# teensyLC-midi-IO_02.net
KiCad netlist of a schematic drawn in EAGLE
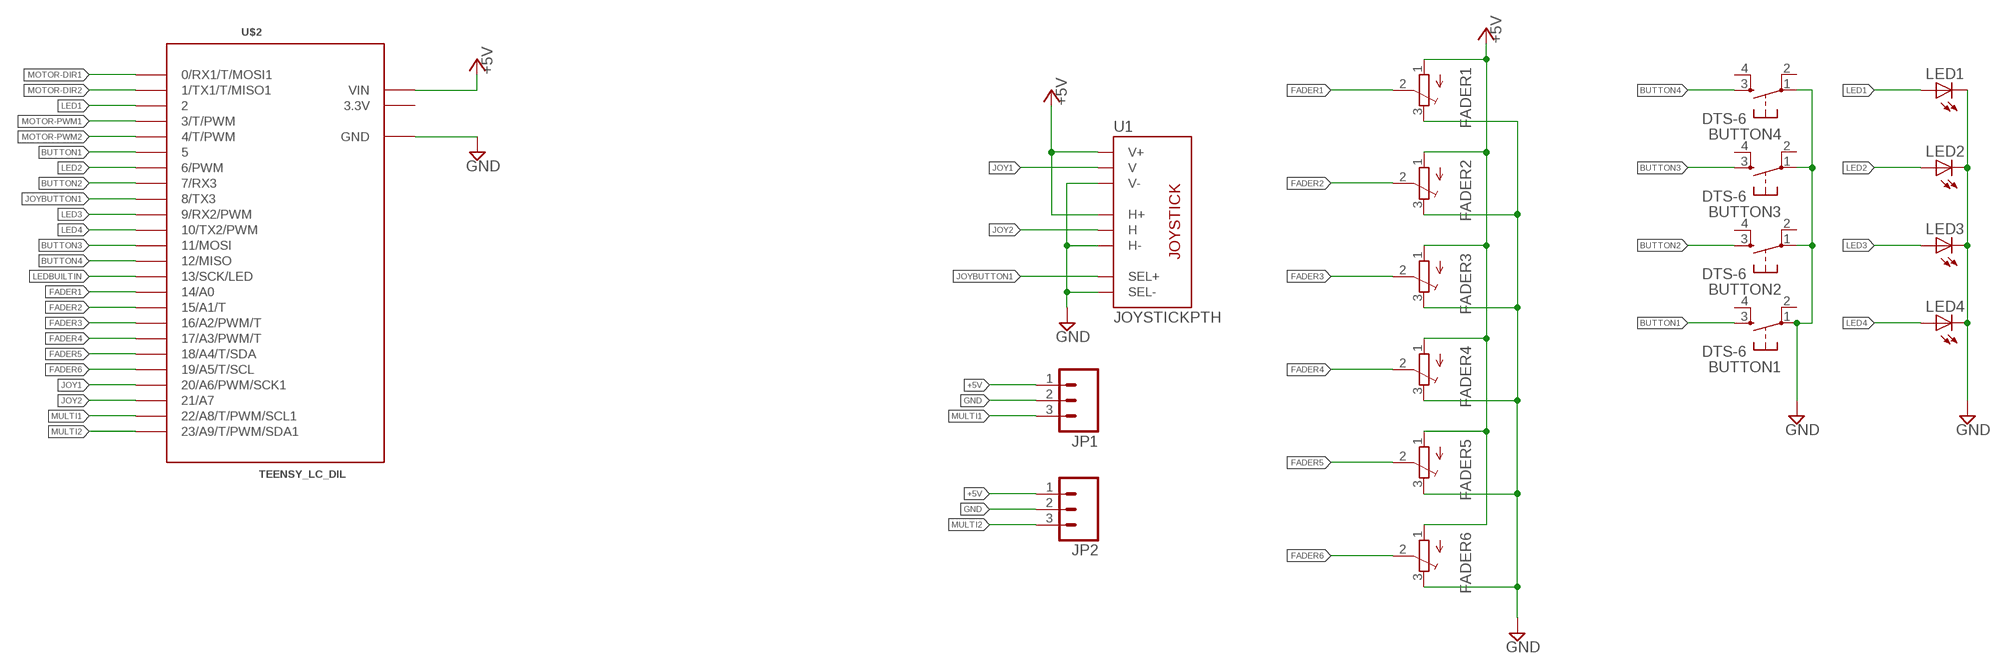
[diagram p0: schematic, sheet 1]

(export (version "E")
  (design (tool "Eeschema 10.0.6"))
  (components
    (comp (ref "BUTTON1")
      (value "DTS-6")
      (footprint "eagle-import:DTS-6")
      (libsource (lib "eagle-import") (part "DTS-6"))
    )
    (comp (ref "BUTTON2")
      (value "DTS-6")
      (footprint "eagle-import:DTS-6")
      (libsource (lib "eagle-import") (part "DTS-6"))
    )
    (comp (ref "BUTTON3")
      (value "DTS-6")
      (footprint "eagle-import:DTS-6")
      (libsource (lib "eagle-import") (part "DTS-6"))
    )
    (comp (ref "BUTTON4")
      (value "DTS-6")
      (footprint "eagle-import:DTS-6")
      (libsource (lib "eagle-import") (part "DTS-6"))
    )
    (comp (ref "FADER1")
      (value "TRIMPOT3386")
      (footprint "eagle-import:TRIM-3386")
      (libsource (lib "eagle-import") (part "TRIMPOT3386"))
    )
    (comp (ref "FADER2")
      (value "TRIMPOT3386")
      (footprint "eagle-import:TRIM-3386")
      (libsource (lib "eagle-import") (part "TRIMPOT3386"))
    )
    (comp (ref "FADER3")
      (value "TRIMPOT3386")
      (footprint "eagle-import:TRIM-3386")
      (libsource (lib "eagle-import") (part "TRIMPOT3386"))
    )
    (comp (ref "FADER4")
      (value "TRIMPOT3386")
      (footprint "eagle-import:TRIM-3386")
      (libsource (lib "eagle-import") (part "TRIMPOT3386"))
    )
    (comp (ref "FADER5")
      (value "TRIMPOT3386")
      (footprint "eagle-import:TRIM-3386")
      (libsource (lib "eagle-import") (part "TRIMPOT3386"))
    )
    (comp (ref "FADER6")
      (value "TRIMPOT3386")
      (footprint "eagle-import:TRIM-3386")
      (libsource (lib "eagle-import") (part "TRIMPOT3386"))
    )
    (comp (ref "JP1")
      (value "M03LOCK")
      (footprint "eagle-import:1X03_LOCK")
      (libsource (lib "eagle-import") (part "M03LOCK"))
    )
    (comp (ref "JP2")
      (value "M03LOCK")
      (footprint "eagle-import:1X03_LOCK")
      (libsource (lib "eagle-import") (part "M03LOCK"))
    )
    (comp (ref "LED1")
      (value "LED5MM")
      (footprint "eagle-import:LED5MM")
      (libsource (lib "eagle-import") (part "LED5MM"))
    )
    (comp (ref "LED2")
      (value "LED5MM")
      (footprint "eagle-import:LED5MM")
      (libsource (lib "eagle-import") (part "LED5MM"))
    )
    (comp (ref "LED3")
      (value "LED5MM")
      (footprint "eagle-import:LED5MM")
      (libsource (lib "eagle-import") (part "LED5MM"))
    )
    (comp (ref "LED4")
      (value "LED5MM")
      (footprint "eagle-import:LED5MM")
      (libsource (lib "eagle-import") (part "LED5MM"))
    )
    (comp (ref "U$2")
      (value "TEENSY_LC_DIL")
      (footprint "eagle-import:TEENSY_3.0-3.2&LC_DIL")
      (libsource (lib "eagle-import") (part "TEENSY_LC_DIL"))
    )
    (comp (ref "U1")
      (value "JOYSTICKPTH")
      (footprint "eagle-import:JOYSTICK")
      (libsource (lib "eagle-import") (part "JOYSTICKPTH"))
    )
  )
  (nets
    (net (code "1") (name "+5V") (class "Default")
      (node (ref "FADER1") (pin "1") (pinfunction "A_1") (pintype "passive"))
      (node (ref "FADER2") (pin "1") (pinfunction "A_1") (pintype "passive"))
      (node (ref "FADER3") (pin "1") (pinfunction "A_1") (pintype "passive"))
      (node (ref "FADER4") (pin "1") (pinfunction "A_1") (pintype "passive"))
      (node (ref "FADER5") (pin "1") (pinfunction "A_1") (pintype "passive"))
      (node (ref "FADER6") (pin "1") (pinfunction "A_1") (pintype "passive"))
      (node (ref "JP1") (pin "1") (pinfunction "1_1") (pintype "passive"))
      (node (ref "JP2") (pin "1") (pinfunction "1_1") (pintype "passive"))
      (node (ref "U$2") (pin "VIN") (pinfunction "VIN_VIN") (pintype "power_in"))
      (node (ref "U1") (pin "H1") (pinfunction "H+_H1") (pintype "bidirectional"))
      (node (ref "U1") (pin "V1") (pinfunction "V+_V1") (pintype "bidirectional"))
    )
    (net (code "2") (name "/3.3V") (class "Default")
      (node (ref "U$2") (pin "3.3V") (pinfunction "3.3V_3.3V") (pintype "power_in"))
    )
    (net (code "3") (name "BUTTON1") (class "Default")
      (node (ref "BUTTON1") (pin "3") (pinfunction "3_3") (pintype "passive"))
      (node (ref "U$2") (pin "5") (pinfunction "5_5") (pintype "bidirectional"))
    )
    (net (code "4") (name "BUTTON2") (class "Default")
      (node (ref "BUTTON2") (pin "3") (pinfunction "3_3") (pintype "passive"))
      (node (ref "U$2") (pin "7") (pinfunction "7/RX3_7") (pintype "bidirectional"))
    )
    (net (code "5") (name "BUTTON3") (class "Default")
      (node (ref "BUTTON3") (pin "3") (pinfunction "3_3") (pintype "passive"))
      (node (ref "U$2") (pin "11") (pinfunction "11/MOSI_11") (pintype "bidirectional"))
    )
    (net (code "6") (name "BUTTON4") (class "Default")
      (node (ref "BUTTON4") (pin "3") (pinfunction "3_3") (pintype "passive"))
      (node (ref "U$2") (pin "12") (pinfunction "12/MISO_12") (pintype "bidirectional"))
    )
    (net (code "7") (name "FADER1") (class "Default")
      (node (ref "FADER1") (pin "2") (pinfunction "S_2") (pintype "passive"))
      (node (ref "U$2") (pin "14/A0") (pinfunction "14/A0_14/A0") (pintype "bidirectional"))
    )
    (net (code "8") (name "FADER2") (class "Default")
      (node (ref "FADER2") (pin "2") (pinfunction "S_2") (pintype "passive"))
      (node (ref "U$2") (pin "15/A1") (pinfunction "15/A1/T_15/A1") (pintype "bidirectional"))
    )
    (net (code "9") (name "FADER3") (class "Default")
      (node (ref "FADER3") (pin "2") (pinfunction "S_2") (pintype "passive"))
      (node (ref "U$2") (pin "16/A2") (pinfunction "16/A2/PWM/T_16/A2") (pintype "bidirectional"))
    )
    (net (code "10") (name "FADER4") (class "Default")
      (node (ref "FADER4") (pin "2") (pinfunction "S_2") (pintype "passive"))
      (node (ref "U$2") (pin "17/A3") (pinfunction "17/A3/PWM/T_17/A3") (pintype "bidirectional"))
    )
    (net (code "11") (name "FADER5") (class "Default")
      (node (ref "FADER5") (pin "2") (pinfunction "S_2") (pintype "passive"))
      (node (ref "U$2") (pin "18/A4") (pinfunction "18/A4/T/SDA_18/A4") (pintype "bidirectional"))
    )
    (net (code "12") (name "FADER6") (class "Default")
      (node (ref "FADER6") (pin "2") (pinfunction "S_2") (pintype "passive"))
      (node (ref "U$2") (pin "19/A5") (pinfunction "19/A5/T/SCL_19/A5") (pintype "bidirectional"))
    )
    (net (code "13") (name "GND") (class "Default")
      (node (ref "BUTTON1") (pin "1") (pinfunction "1_1") (pintype "passive"))
      (node (ref "BUTTON2") (pin "1") (pinfunction "1_1") (pintype "passive"))
      (node (ref "BUTTON3") (pin "1") (pinfunction "1_1") (pintype "passive"))
      (node (ref "BUTTON4") (pin "1") (pinfunction "1_1") (pintype "passive"))
      (node (ref "FADER1") (pin "3") (pinfunction "E_3") (pintype "passive"))
      (node (ref "FADER2") (pin "3") (pinfunction "E_3") (pintype "passive"))
      (node (ref "FADER3") (pin "3") (pinfunction "E_3") (pintype "passive"))
      (node (ref "FADER4") (pin "3") (pinfunction "E_3") (pintype "passive"))
      (node (ref "FADER5") (pin "3") (pinfunction "E_3") (pintype "passive"))
      (node (ref "FADER6") (pin "3") (pinfunction "E_3") (pintype "passive"))
      (node (ref "JP1") (pin "2") (pinfunction "2_2") (pintype "passive"))
      (node (ref "JP2") (pin "2") (pinfunction "2_2") (pintype "passive"))
      (node (ref "LED1") (pin "K") (pinfunction "C_K") (pintype "passive"))
      (node (ref "LED2") (pin "K") (pinfunction "C_K") (pintype "passive"))
      (node (ref "LED3") (pin "K") (pinfunction "C_K") (pintype "passive"))
      (node (ref "LED4") (pin "K") (pinfunction "C_K") (pintype "passive"))
      (node (ref "U$2") (pin "AGND") (pinfunction "GND_AGND") (pintype "power_in"))
      (node (ref "U$2") (pin "GND") (pinfunction "GND_GND") (pintype "power_in"))
      (node (ref "U1") (pin "B2A") (pinfunction "SEL-_B2A") (pintype "bidirectional"))
      (node (ref "U1") (pin "H3") (pinfunction "H-_H3") (pintype "bidirectional"))
      (node (ref "U1") (pin "V3") (pinfunction "V-_V3") (pintype "bidirectional"))
    )
    (net (code "14") (name "JOY1") (class "Default")
      (node (ref "U$2") (pin "20/A6") (pinfunction "20/A6/PWM/SCK1_20/A6") (pintype "bidirectional"))
      (node (ref "U1") (pin "V2") (pinfunction "V_V2") (pintype "bidirectional"))
    )
    (net (code "15") (name "JOY2") (class "Default")
      (node (ref "U$2") (pin "21/A7") (pinfunction "21/A7_21/A7") (pintype "bidirectional"))
      (node (ref "U1") (pin "H2") (pinfunction "H_H2") (pintype "bidirectional"))
    )
    (net (code "16") (name "JOYBUTTON1") (class "Default")
      (node (ref "U$2") (pin "8") (pinfunction "8/TX3_8") (pintype "bidirectional"))
      (node (ref "U1") (pin "B1A") (pinfunction "SEL+_B1A") (pintype "bidirectional"))
    )
    (net (code "17") (name "LED1") (class "Default")
      (node (ref "LED1") (pin "A") (pinfunction "A_A") (pintype "passive"))
      (node (ref "U$2") (pin "2") (pinfunction "2_2") (pintype "bidirectional"))
    )
    (net (code "18") (name "LED2") (class "Default")
      (node (ref "LED2") (pin "A") (pinfunction "A_A") (pintype "passive"))
      (node (ref "U$2") (pin "6") (pinfunction "6/PWM_6") (pintype "bidirectional"))
    )
    (net (code "19") (name "LED3") (class "Default")
      (node (ref "LED3") (pin "A") (pinfunction "A_A") (pintype "passive"))
      (node (ref "U$2") (pin "9") (pinfunction "9/RX2/PWM_9") (pintype "bidirectional"))
    )
    (net (code "20") (name "LED4") (class "Default")
      (node (ref "LED4") (pin "A") (pinfunction "A_A") (pintype "passive"))
      (node (ref "U$2") (pin "10") (pinfunction "10/TX2/PWM_10") (pintype "bidirectional"))
    )
    (net (code "21") (name "LEDBUILTIN") (class "Default")
      (node (ref "U$2") (pin "13") (pinfunction "13/SCK/LED_13") (pintype "bidirectional"))
    )
    (net (code "22") (name "MOTOR-DIR1") (class "Default")
      (node (ref "U$2") (pin "0") (pinfunction "0/RX1/T/MOSI1_0") (pintype "bidirectional"))
    )
    (net (code "23") (name "MOTOR-DIR2") (class "Default")
      (node (ref "U$2") (pin "1") (pinfunction "1/TX1/T/MISO1_1") (pintype "bidirectional"))
    )
    (net (code "24") (name "MOTOR-PWM1") (class "Default")
      (node (ref "U$2") (pin "3") (pinfunction "3/T/PWM_3") (pintype "bidirectional"))
    )
    (net (code "25") (name "MOTOR-PWM2") (class "Default")
      (node (ref "U$2") (pin "4") (pinfunction "4/T/PWM_4") (pintype "bidirectional"))
    )
    (net (code "26") (name "MULTI1") (class "Default")
      (node (ref "JP1") (pin "3") (pinfunction "3_3") (pintype "passive"))
      (node (ref "U$2") (pin "22/A8") (pinfunction "22/A8/T/PWM/SCL1_22/A8") (pintype "bidirectional"))
    )
    (net (code "27") (name "MULTI2") (class "Default")
      (node (ref "JP2") (pin "3") (pinfunction "3_3") (pintype "passive"))
      (node (ref "U$2") (pin "23/A9") (pinfunction "23/A9/T/PWM/SDA1_23/A9") (pintype "bidirectional"))
    )
    (net (code "28") (name "unconnected-(BUTTON1-Pad2)") (class "Default")
      (node (ref "BUTTON1") (pin "2") (pinfunction "2_2") (pintype "passive"))
    )
    (net (code "29") (name "unconnected-(BUTTON1-Pad4)") (class "Default")
      (node (ref "BUTTON1") (pin "4") (pinfunction "4_4") (pintype "passive"))
    )
    (net (code "30") (name "unconnected-(BUTTON2-Pad2)") (class "Default")
      (node (ref "BUTTON2") (pin "2") (pinfunction "2_2") (pintype "passive"))
    )
    (net (code "31") (name "unconnected-(BUTTON2-Pad4)") (class "Default")
      (node (ref "BUTTON2") (pin "4") (pinfunction "4_4") (pintype "passive"))
    )
    (net (code "32") (name "unconnected-(BUTTON3-Pad2)") (class "Default")
      (node (ref "BUTTON3") (pin "2") (pinfunction "2_2") (pintype "passive"))
    )
    (net (code "33") (name "unconnected-(BUTTON3-Pad4)") (class "Default")
      (node (ref "BUTTON3") (pin "4") (pinfunction "4_4") (pintype "passive"))
    )
    (net (code "34") (name "unconnected-(BUTTON4-Pad2)") (class "Default")
      (node (ref "BUTTON4") (pin "2") (pinfunction "2_2") (pintype "passive"))
    )
    (net (code "35") (name "unconnected-(BUTTON4-Pad4)") (class "Default")
      (node (ref "BUTTON4") (pin "4") (pinfunction "4_4") (pintype "passive"))
    )
  )
)
